# touch.net
KiCad netlist of a schematic drawn in Altium Designer
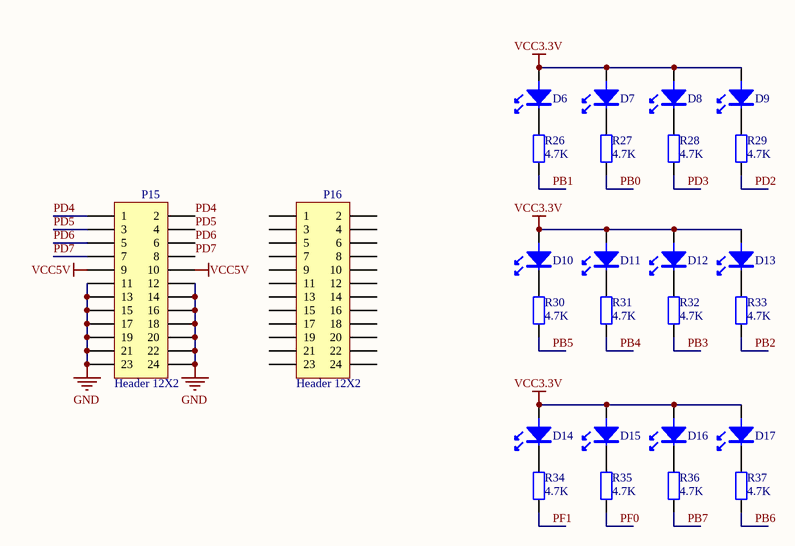
[diagram p0: touch.SchDoc]

(export (version "E")
  (design (tool "Eeschema 10.0.6"))
  (components
    (comp (ref "D6")
      (value "LED")
      (footprint "0603_LED_S1")
      (description "贴片LED，0603，白色")
      (libsource (lib "stm8l052r8t6开发板") (part "LED"))
    )
    (comp (ref "D7")
      (value "LED")
      (footprint "0603_LED_S1")
      (description "贴片LED，0603，白色")
      (libsource (lib "stm8l052r8t6开发板") (part "LED"))
    )
    (comp (ref "D8")
      (value "LED")
      (footprint "0603_LED_S1")
      (description "贴片LED，0603，白色")
      (libsource (lib "stm8l052r8t6开发板") (part "LED"))
    )
    (comp (ref "D9")
      (value "LED")
      (footprint "0603_LED_S1")
      (description "贴片LED，0603，白色")
      (libsource (lib "stm8l052r8t6开发板") (part "LED"))
    )
    (comp (ref "D10")
      (value "LED")
      (footprint "0603_LED_S1")
      (description "贴片LED，0603，白色")
      (libsource (lib "stm8l052r8t6开发板") (part "LED"))
    )
    (comp (ref "D11")
      (value "LED")
      (footprint "0603_LED_S1")
      (description "贴片LED，0603，白色")
      (libsource (lib "stm8l052r8t6开发板") (part "LED"))
    )
    (comp (ref "D12")
      (value "LED")
      (footprint "0603_LED_S1")
      (description "贴片LED，0603，白色")
      (libsource (lib "stm8l052r8t6开发板") (part "LED"))
    )
    (comp (ref "D13")
      (value "LED")
      (footprint "0603_LED_S1")
      (description "贴片LED，0603，白色")
      (libsource (lib "stm8l052r8t6开发板") (part "LED"))
    )
    (comp (ref "D14")
      (value "LED")
      (footprint "0603_LED_S1")
      (description "贴片LED，0603，白色")
      (libsource (lib "stm8l052r8t6开发板") (part "LED"))
    )
    (comp (ref "D15")
      (value "LED")
      (footprint "0603_LED_S1")
      (description "贴片LED，0603，白色")
      (libsource (lib "stm8l052r8t6开发板") (part "LED"))
    )
    (comp (ref "D16")
      (value "LED")
      (footprint "0603_LED_S1")
      (description "贴片LED，0603，白色")
      (libsource (lib "stm8l052r8t6开发板") (part "LED"))
    )
    (comp (ref "D17")
      (value "LED")
      (footprint "0603_LED_S1")
      (description "贴片LED，0603，白色")
      (libsource (lib "stm8l052r8t6开发板") (part "LED"))
    )
    (comp (ref "P15")
      (value "Header 12X2")
      (footprint "2.0mm 2*12P直排母")
      (description "Header, 12-Pin, Dual row")
      (fields (field (name "PUBLISHER") "Altium Limited"))
      (libsource (lib "Miscellaneous Connectors") (part "Header 12X2"))
    )
    (comp (ref "P16")
      (value "Header 12X2")
      (footprint "2.0mm 2*12P直排母")
      (description "Header, 12-Pin, Dual row")
      (fields (field (name "PUBLISHER") "Altium Limited"))
      (libsource (lib "Miscellaneous Connectors") (part "Header 12X2"))
    )
    (comp (ref "R26")
      (value "4.7K")
      (footprint "0603_R")
      (description "贴片电阻，0603")
      (libsource (lib "stm8l052r8t6开发板") (part "Res2"))
    )
    (comp (ref "R27")
      (value "4.7K")
      (footprint "0603_R")
      (description "贴片电阻，0603")
      (libsource (lib "stm8l052r8t6开发板") (part "Res2"))
    )
    (comp (ref "R28")
      (value "4.7K")
      (footprint "0603_R")
      (description "贴片电阻，0603")
      (libsource (lib "stm8l052r8t6开发板") (part "Res2"))
    )
    (comp (ref "R29")
      (value "4.7K")
      (footprint "0603_R")
      (description "贴片电阻，0603")
      (libsource (lib "stm8l052r8t6开发板") (part "Res2"))
    )
    (comp (ref "R30")
      (value "4.7K")
      (footprint "0603_R")
      (description "贴片电阻，0603")
      (libsource (lib "stm8l052r8t6开发板") (part "Res2"))
    )
    (comp (ref "R31")
      (value "4.7K")
      (footprint "0603_R")
      (description "贴片电阻，0603")
      (libsource (lib "stm8l052r8t6开发板") (part "Res2"))
    )
    (comp (ref "R32")
      (value "4.7K")
      (footprint "0603_R")
      (description "贴片电阻，0603")
      (libsource (lib "stm8l052r8t6开发板") (part "Res2"))
    )
    (comp (ref "R33")
      (value "4.7K")
      (footprint "0603_R")
      (description "贴片电阻，0603")
      (libsource (lib "stm8l052r8t6开发板") (part "Res2"))
    )
    (comp (ref "R34")
      (value "4.7K")
      (footprint "0603_R")
      (description "贴片电阻，0603")
      (libsource (lib "stm8l052r8t6开发板") (part "Res2"))
    )
    (comp (ref "R35")
      (value "4.7K")
      (footprint "0603_R")
      (description "贴片电阻，0603")
      (libsource (lib "stm8l052r8t6开发板") (part "Res2"))
    )
    (comp (ref "R36")
      (value "4.7K")
      (footprint "0603_R")
      (description "贴片电阻，0603")
      (libsource (lib "stm8l052r8t6开发板") (part "Res2"))
    )
    (comp (ref "R37")
      (value "4.7K")
      (footprint "0603_R")
      (description "贴片电阻，0603")
      (libsource (lib "stm8l052r8t6开发板") (part "Res2"))
    )
  )
  (nets
    (net (code "1") (name "/PB0") (class "Default")
      (node (ref "R27") (pin "1") (pinfunction "1_1") (pintype "passive"))
    )
    (net (code "2") (name "/PB1") (class "Default")
      (node (ref "R26") (pin "1") (pinfunction "1_1") (pintype "passive"))
    )
    (net (code "3") (name "/PB2") (class "Default")
      (node (ref "R33") (pin "1") (pinfunction "1_1") (pintype "passive"))
    )
    (net (code "4") (name "/PB3") (class "Default")
      (node (ref "R32") (pin "1") (pinfunction "1_1") (pintype "passive"))
    )
    (net (code "5") (name "/PB4") (class "Default")
      (node (ref "R31") (pin "1") (pinfunction "1_1") (pintype "passive"))
    )
    (net (code "6") (name "/PB5") (class "Default")
      (node (ref "R30") (pin "1") (pinfunction "1_1") (pintype "passive"))
    )
    (net (code "7") (name "/PB6") (class "Default")
      (node (ref "R37") (pin "1") (pinfunction "1_1") (pintype "passive"))
    )
    (net (code "8") (name "/PB7") (class "Default")
      (node (ref "R36") (pin "1") (pinfunction "1_1") (pintype "passive"))
    )
    (net (code "9") (name "/PD2") (class "Default")
      (node (ref "R29") (pin "1") (pinfunction "1_1") (pintype "passive"))
    )
    (net (code "10") (name "/PD3") (class "Default")
      (node (ref "R28") (pin "1") (pinfunction "1_1") (pintype "passive"))
    )
    (net (code "11") (name "/PD4") (class "Default")
      (node (ref "P15") (pin "1") (pinfunction "1_1") (pintype "passive"))
      (node (ref "P15") (pin "2") (pinfunction "2_2") (pintype "passive"))
    )
    (net (code "12") (name "/PD5") (class "Default")
      (node (ref "P15") (pin "3") (pinfunction "3_3") (pintype "passive"))
      (node (ref "P15") (pin "4") (pinfunction "4_4") (pintype "passive"))
    )
    (net (code "13") (name "/PD6") (class "Default")
      (node (ref "P15") (pin "5") (pinfunction "5_5") (pintype "passive"))
      (node (ref "P15") (pin "6") (pinfunction "6_6") (pintype "passive"))
    )
    (net (code "14") (name "/PD7") (class "Default")
      (node (ref "P15") (pin "7") (pinfunction "7_7") (pintype "passive"))
      (node (ref "P15") (pin "8") (pinfunction "8_8") (pintype "passive"))
    )
    (net (code "15") (name "/PF0") (class "Default")
      (node (ref "R35") (pin "1") (pinfunction "1_1") (pintype "passive"))
    )
    (net (code "16") (name "/PF1") (class "Default")
      (node (ref "R34") (pin "1") (pinfunction "1_1") (pintype "passive"))
    )
    (net (code "17") (name "GND") (class "Default")
      (node (ref "P15") (pin "11") (pinfunction "11_11") (pintype "passive"))
      (node (ref "P15") (pin "12") (pinfunction "12_12") (pintype "passive"))
      (node (ref "P15") (pin "13") (pinfunction "13_13") (pintype "passive"))
      (node (ref "P15") (pin "14") (pinfunction "14_14") (pintype "passive"))
      (node (ref "P15") (pin "15") (pinfunction "15_15") (pintype "passive"))
      (node (ref "P15") (pin "16") (pinfunction "16_16") (pintype "passive"))
      (node (ref "P15") (pin "17") (pinfunction "17_17") (pintype "passive"))
      (node (ref "P15") (pin "18") (pinfunction "18_18") (pintype "passive"))
      (node (ref "P15") (pin "19") (pinfunction "19_19") (pintype "passive"))
      (node (ref "P15") (pin "20") (pinfunction "20_20") (pintype "passive"))
      (node (ref "P15") (pin "21") (pinfunction "21_21") (pintype "passive"))
      (node (ref "P15") (pin "22") (pinfunction "22_22") (pintype "passive"))
      (node (ref "P15") (pin "23") (pinfunction "23_23") (pintype "passive"))
      (node (ref "P15") (pin "24") (pinfunction "24_24") (pintype "passive"))
    )
    (net (code "18") (name "Net-(D6-PadK)") (class "Default")
      (node (ref "D6") (pin "K") (pinfunction "K_K") (pintype "passive"))
      (node (ref "R26") (pin "2") (pinfunction "2_2") (pintype "passive"))
    )
    (net (code "19") (name "Net-(D7-PadK)") (class "Default")
      (node (ref "D7") (pin "K") (pinfunction "K_K") (pintype "passive"))
      (node (ref "R27") (pin "2") (pinfunction "2_2") (pintype "passive"))
    )
    (net (code "20") (name "Net-(D8-PadK)") (class "Default")
      (node (ref "D8") (pin "K") (pinfunction "K_K") (pintype "passive"))
      (node (ref "R28") (pin "2") (pinfunction "2_2") (pintype "passive"))
    )
    (net (code "21") (name "Net-(D9-PadK)") (class "Default")
      (node (ref "D9") (pin "K") (pinfunction "K_K") (pintype "passive"))
      (node (ref "R29") (pin "2") (pinfunction "2_2") (pintype "passive"))
    )
    (net (code "22") (name "Net-(D10-PadK)") (class "Default")
      (node (ref "D10") (pin "K") (pinfunction "K_K") (pintype "passive"))
      (node (ref "R30") (pin "2") (pinfunction "2_2") (pintype "passive"))
    )
    (net (code "23") (name "Net-(D11-PadK)") (class "Default")
      (node (ref "D11") (pin "K") (pinfunction "K_K") (pintype "passive"))
      (node (ref "R31") (pin "2") (pinfunction "2_2") (pintype "passive"))
    )
    (net (code "24") (name "Net-(D12-PadK)") (class "Default")
      (node (ref "D12") (pin "K") (pinfunction "K_K") (pintype "passive"))
      (node (ref "R32") (pin "2") (pinfunction "2_2") (pintype "passive"))
    )
    (net (code "25") (name "Net-(D13-PadK)") (class "Default")
      (node (ref "D13") (pin "K") (pinfunction "K_K") (pintype "passive"))
      (node (ref "R33") (pin "2") (pinfunction "2_2") (pintype "passive"))
    )
    (net (code "26") (name "Net-(D14-PadK)") (class "Default")
      (node (ref "D14") (pin "K") (pinfunction "K_K") (pintype "passive"))
      (node (ref "R34") (pin "2") (pinfunction "2_2") (pintype "passive"))
    )
    (net (code "27") (name "Net-(D15-PadK)") (class "Default")
      (node (ref "D15") (pin "K") (pinfunction "K_K") (pintype "passive"))
      (node (ref "R35") (pin "2") (pinfunction "2_2") (pintype "passive"))
    )
    (net (code "28") (name "Net-(D16-PadK)") (class "Default")
      (node (ref "D16") (pin "K") (pinfunction "K_K") (pintype "passive"))
      (node (ref "R36") (pin "2") (pinfunction "2_2") (pintype "passive"))
    )
    (net (code "29") (name "Net-(D17-PadK)") (class "Default")
      (node (ref "D17") (pin "K") (pinfunction "K_K") (pintype "passive"))
      (node (ref "R37") (pin "2") (pinfunction "2_2") (pintype "passive"))
    )
    (net (code "30") (name "VCC3.3V") (class "Default")
      (node (ref "D10") (pin "A") (pinfunction "A_A") (pintype "passive"))
      (node (ref "D11") (pin "A") (pinfunction "A_A") (pintype "passive"))
      (node (ref "D12") (pin "A") (pinfunction "A_A") (pintype "passive"))
      (node (ref "D13") (pin "A") (pinfunction "A_A") (pintype "passive"))
      (node (ref "D14") (pin "A") (pinfunction "A_A") (pintype "passive"))
      (node (ref "D15") (pin "A") (pinfunction "A_A") (pintype "passive"))
      (node (ref "D16") (pin "A") (pinfunction "A_A") (pintype "passive"))
      (node (ref "D17") (pin "A") (pinfunction "A_A") (pintype "passive"))
      (node (ref "D6") (pin "A") (pinfunction "A_A") (pintype "passive"))
      (node (ref "D7") (pin "A") (pinfunction "A_A") (pintype "passive"))
      (node (ref "D8") (pin "A") (pinfunction "A_A") (pintype "passive"))
      (node (ref "D9") (pin "A") (pinfunction "A_A") (pintype "passive"))
    )
    (net (code "31") (name "VCC5V") (class "Default")
      (node (ref "P15") (pin "10") (pinfunction "10_10") (pintype "passive"))
      (node (ref "P15") (pin "9") (pinfunction "9_9") (pintype "passive"))
    )
    (net (code "32") (name "unconnected-(P16-Pad1)") (class "Default")
      (node (ref "P16") (pin "1") (pinfunction "1_1") (pintype "passive"))
    )
    (net (code "33") (name "unconnected-(P16-Pad2)") (class "Default")
      (node (ref "P16") (pin "2") (pinfunction "2_2") (pintype "passive"))
    )
    (net (code "34") (name "unconnected-(P16-Pad3)") (class "Default")
      (node (ref "P16") (pin "3") (pinfunction "3_3") (pintype "passive"))
    )
    (net (code "35") (name "unconnected-(P16-Pad4)") (class "Default")
      (node (ref "P16") (pin "4") (pinfunction "4_4") (pintype "passive"))
    )
    (net (code "36") (name "unconnected-(P16-Pad5)") (class "Default")
      (node (ref "P16") (pin "5") (pinfunction "5_5") (pintype "passive"))
    )
    (net (code "37") (name "unconnected-(P16-Pad6)") (class "Default")
      (node (ref "P16") (pin "6") (pinfunction "6_6") (pintype "passive"))
    )
    (net (code "38") (name "unconnected-(P16-Pad7)") (class "Default")
      (node (ref "P16") (pin "7") (pinfunction "7_7") (pintype "passive"))
    )
    (net (code "39") (name "unconnected-(P16-Pad8)") (class "Default")
      (node (ref "P16") (pin "8") (pinfunction "8_8") (pintype "passive"))
    )
    (net (code "40") (name "unconnected-(P16-Pad9)") (class "Default")
      (node (ref "P16") (pin "9") (pinfunction "9_9") (pintype "passive"))
    )
    (net (code "41") (name "unconnected-(P16-Pad10)") (class "Default")
      (node (ref "P16") (pin "10") (pinfunction "10_10") (pintype "passive"))
    )
    (net (code "42") (name "unconnected-(P16-Pad11)") (class "Default")
      (node (ref "P16") (pin "11") (pinfunction "11_11") (pintype "passive"))
    )
    (net (code "43") (name "unconnected-(P16-Pad12)") (class "Default")
      (node (ref "P16") (pin "12") (pinfunction "12_12") (pintype "passive"))
    )
    (net (code "44") (name "unconnected-(P16-Pad13)") (class "Default")
      (node (ref "P16") (pin "13") (pinfunction "13_13") (pintype "passive"))
    )
    (net (code "45") (name "unconnected-(P16-Pad14)") (class "Default")
      (node (ref "P16") (pin "14") (pinfunction "14_14") (pintype "passive"))
    )
    (net (code "46") (name "unconnected-(P16-Pad15)") (class "Default")
      (node (ref "P16") (pin "15") (pinfunction "15_15") (pintype "passive"))
    )
    (net (code "47") (name "unconnected-(P16-Pad16)") (class "Default")
      (node (ref "P16") (pin "16") (pinfunction "16_16") (pintype "passive"))
    )
    (net (code "48") (name "unconnected-(P16-Pad17)") (class "Default")
      (node (ref "P16") (pin "17") (pinfunction "17_17") (pintype "passive"))
    )
    (net (code "49") (name "unconnected-(P16-Pad18)") (class "Default")
      (node (ref "P16") (pin "18") (pinfunction "18_18") (pintype "passive"))
    )
    (net (code "50") (name "unconnected-(P16-Pad19)") (class "Default")
      (node (ref "P16") (pin "19") (pinfunction "19_19") (pintype "passive"))
    )
    (net (code "51") (name "unconnected-(P16-Pad20)") (class "Default")
      (node (ref "P16") (pin "20") (pinfunction "20_20") (pintype "passive"))
    )
    (net (code "52") (name "unconnected-(P16-Pad21)") (class "Default")
      (node (ref "P16") (pin "21") (pinfunction "21_21") (pintype "passive"))
    )
    (net (code "53") (name "unconnected-(P16-Pad22)") (class "Default")
      (node (ref "P16") (pin "22") (pinfunction "22_22") (pintype "passive"))
    )
    (net (code "54") (name "unconnected-(P16-Pad23)") (class "Default")
      (node (ref "P16") (pin "23") (pinfunction "23_23") (pintype "passive"))
    )
    (net (code "55") (name "unconnected-(P16-Pad24)") (class "Default")
      (node (ref "P16") (pin "24") (pinfunction "24_24") (pintype "passive"))
    )
  )
)
